# Power_Left.net
KiCad netlist of a schematic drawn in Altium Designer
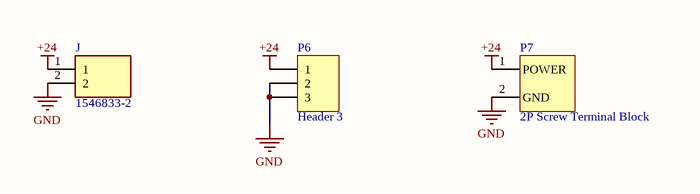
[diagram p0: Power_Left.SchDoc]

(export (version "E")
  (design (tool "Eeschema 10.0.6"))
  (components
    (comp (ref "J")
      (value "1546833-2")
      (footprint "TE_1546833-2")
      (description "2 Circuit 0.375 (9.53mm) Barrier Block Connector, Screws with Captive Plate")
      (fields (field (name "MF") "TE Connectivity"))
      (libsource (lib "1546833-2") (part "1546833-2"))
    )
    (comp (ref "P6")
      (value "Header 3")
      (footprint "HDR1X3")
      (description "Header, 3-Pin")
      (fields (field (name "PUBLISHER") "Altium Limited"))
      (libsource (lib "Miscellaneous Connectors") (part "Header 3"))
    )
    (comp (ref "P7")
      (value "2P Screw Terminal Block")
      (footprint "P_Terminal block 3.5mm-pitch")
      (description "Green Straight pin 3.5mm  pitch; P=3.5mm  Screw terminal ROHS")
      (fields (field (name "MFR PART #") "KF350-3.5-2P") (field (name "MANUFACTURER") "Cixi Kefa Elec"))
      (libsource (lib "ECEN5730Lib_2023_05_DS") (part "P_Terminal block"))
    )
  )
  (nets
    (net (code "1") (name "+24") (class "Default")
      (node (ref "J") (pin "1") (pinfunction "1_1") (pintype "passive"))
      (node (ref "P6") (pin "1") (pinfunction "1_1") (pintype "passive"))
      (node (ref "P7") (pin "1") (pinfunction "POWER_1") (pintype "passive"))
    )
    (net (code "2") (name "GND") (class "Default")
      (node (ref "J") (pin "2") (pinfunction "2_2") (pintype "passive"))
      (node (ref "P6") (pin "2") (pinfunction "2_2") (pintype "passive"))
      (node (ref "P6") (pin "3") (pinfunction "3_3") (pintype "passive"))
      (node (ref "P7") (pin "2") (pinfunction "GND_2") (pintype "passive"))
    )
  )
)
